# rolety.net
KiCad netlist of a schematic drawn in EAGLE
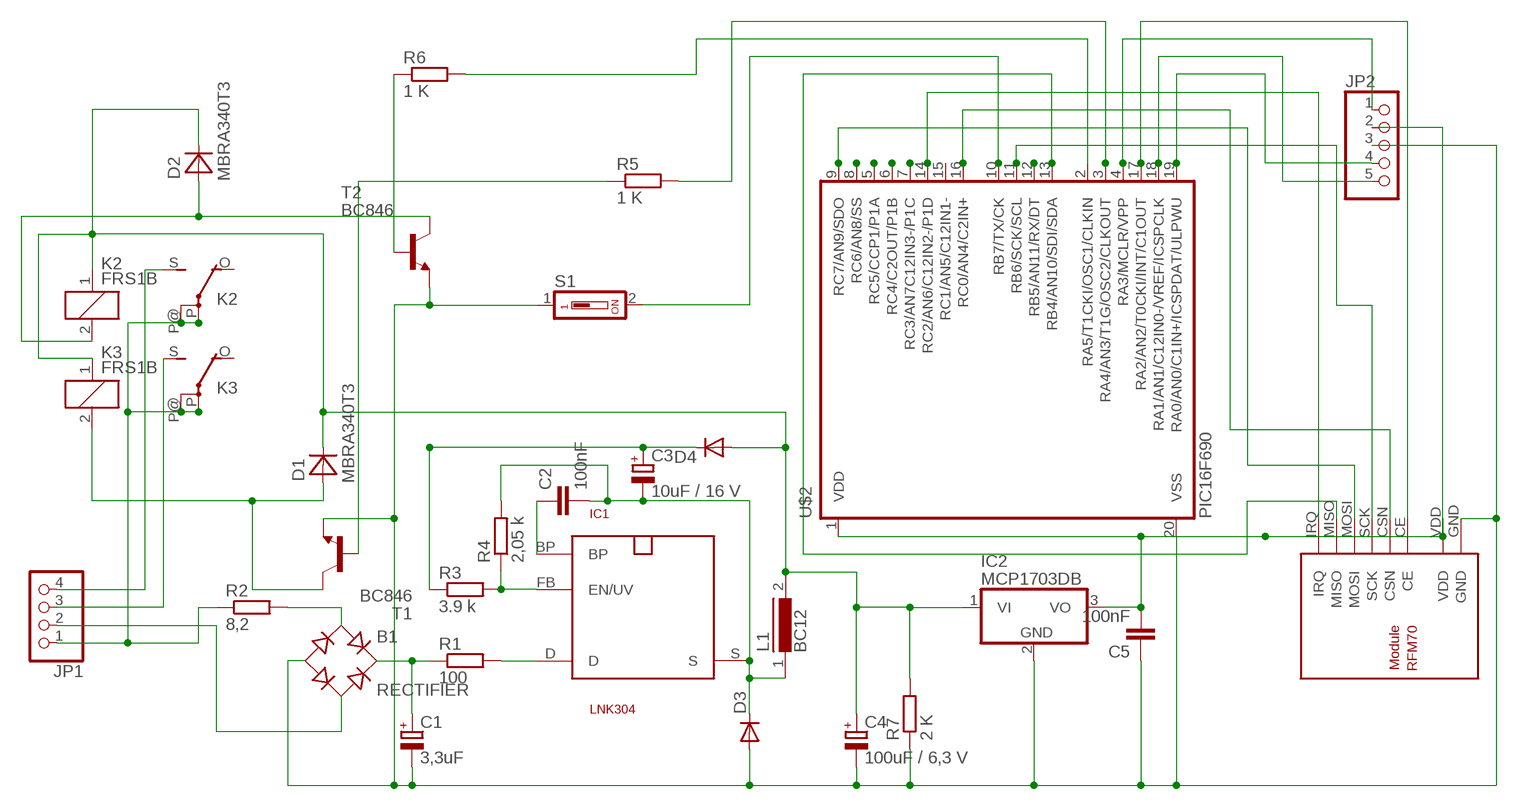
[diagram p0: schematic, sheet 1]

(export (version "E")
  (design (tool "Eeschema 10.0.6"))
  (components
    (comp (ref "B1")
      (value "RECTIFIER")
      (footprint "eagle-import:TO-269AA")
      (libsource (lib "eagle-import") (part "RECTIFIER-S40"))
    )
    (comp (ref "C1")
      (value "3,3uF")
      (footprint "eagle-import:E5-13")
      (libsource (lib "eagle-import") (part "CPOL-EUE5-13"))
    )
    (comp (ref "C2")
      (value "100nF")
      (footprint "eagle-import:C2012")
      (libsource (lib "eagle-import") (part "C-EUC2012"))
    )
    (comp (ref "C3")
      (value "10uF / 16 V")
      (footprint "eagle-import:E2,5-5")
      (libsource (lib "eagle-import") (part "CPOL-EUE2.5-5"))
    )
    (comp (ref "C4")
      (value "100uF / 6,3 V")
      (footprint "eagle-import:E2,5-5")
      (libsource (lib "eagle-import") (part "CPOL-EUE2.5-5"))
    )
    (comp (ref "C5")
      (value "100nF")
      (footprint "eagle-import:C2012")
      (libsource (lib "eagle-import") (part "C-EUC2012"))
    )
    (comp (ref "D1")
      (value "MBRA340T3")
      (footprint "eagle-import:SMA")
      (libsource (lib "eagle-import") (part "MBRA340T3"))
    )
    (comp (ref "D2")
      (value "MBRA340T3")
      (footprint "eagle-import:SMA")
      (libsource (lib "eagle-import") (part "MBRA340T3"))
    )
    (comp (ref "D3")
      (value "DIODE-DO214AA")
      (footprint "eagle-import:DO214AA")
      (libsource (lib "eagle-import") (part "DIODE-DO214AA"))
    )
    (comp (ref "D4")
      (value "DIODE-DO214AA")
      (footprint "eagle-import:DO214AA")
      (libsource (lib "eagle-import") (part "DIODE-DO214AA"))
    )
    (comp (ref "IC1")
      (value "LNK304")
      (footprint "eagle-import:SO-8C")
      (libsource (lib "eagle-import") (part "SO-8C"))
    )
    (comp (ref "IC2")
      (value "MCP1703DB")
      (footprint "eagle-import:SOT223")
      (libsource (lib "eagle-import") (part "MCP1703DB"))
    )
    (comp (ref "JP1")
      (value "PINHD-1X4")
      (footprint "eagle-import:1X04")
      (libsource (lib "eagle-import") (part "PINHD-1X4"))
    )
    (comp (ref "JP2")
      (value "PINHD-1X5")
      (footprint "eagle-import:1X05")
      (libsource (lib "eagle-import") (part "PINHD-1X5"))
    )
    (comp (ref "K2")
      (value "FRS1B")
      (footprint "eagle-import:FRS1B")
      (libsource (lib "eagle-import") (part "FRS1B"))
    )
    (comp (ref "K3")
      (value "FRS1B")
      (footprint "eagle-import:FRS1B")
      (libsource (lib "eagle-import") (part "FRS1B"))
    )
    (comp (ref "L1")
      (value "BC12")
      (footprint "eagle-import:BC12")
      (libsource (lib "eagle-import") (part "BC12"))
    )
    (comp (ref "R1")
      (value "100")
      (footprint "eagle-import:R2512W")
      (libsource (lib "eagle-import") (part "R-EU_R2512W"))
    )
    (comp (ref "R2")
      (value "8,2")
      (footprint "eagle-import:R2512W")
      (libsource (lib "eagle-import") (part "R-EU_R2512W"))
    )
    (comp (ref "R3")
      (value "3.9 k")
      (footprint "eagle-import:M2012")
      (libsource (lib "eagle-import") (part "R-EU_M2012"))
    )
    (comp (ref "R4")
      (value "2,05 k")
      (footprint "eagle-import:M2012")
      (libsource (lib "eagle-import") (part "R-EU_M2012"))
    )
    (comp (ref "R5")
      (value "1 K")
      (footprint "eagle-import:M2012")
      (libsource (lib "eagle-import") (part "R-EU_M2012"))
    )
    (comp (ref "R6")
      (value "1 K")
      (footprint "eagle-import:M2012")
      (libsource (lib "eagle-import") (part "R-EU_M2012"))
    )
    (comp (ref "R7")
      (value "2 K")
      (footprint "eagle-import:M2012")
      (libsource (lib "eagle-import") (part "R-EU_M2012"))
    )
    (comp (ref "S1")
      (value "SD4-01")
      (footprint "eagle-import:SD4-01")
      (libsource (lib "eagle-import") (part "SD4-01"))
    )
    (comp (ref "T1")
      (value "BC846")
      (footprint "eagle-import:SOT23")
      (libsource (lib "eagle-import") (part "BC846"))
    )
    (comp (ref "T2")
      (value "BC846")
      (footprint "eagle-import:SOT23")
      (libsource (lib "eagle-import") (part "BC846"))
    )
    (comp (ref "U$1")
      (value "RFM70")
      (footprint "eagle-import:RFM70")
      (libsource (lib "eagle-import") (part "RFM70"))
    )
    (comp (ref "U$2")
      (value "PIC16F690")
      (footprint "eagle-import:SSOP20")
      (libsource (lib "eagle-import") (part "PIC16F690"))
    )
  )
  (nets
    (net (code "1") (name "Net-(B1-Pad+)") (class "Default")
      (node (ref "B1") (pin "+") (pinfunction "+_+") (pintype "passive"))
      (node (ref "C1") (pin "+") (pinfunction "+_+") (pintype "passive"))
      (node (ref "R1") (pin "1") (pinfunction "1_1") (pintype "passive"))
    )
    (net (code "2") (name "Net-(B1-PadAC1)") (class "Default")
      (node (ref "B1") (pin "AC1") (pinfunction "AC1_AC1") (pintype "passive"))
      (node (ref "R2") (pin "2") (pinfunction "2_2") (pintype "passive"))
    )
    (net (code "3") (name "Net-(B1-PadAC2)") (class "Default")
      (node (ref "B1") (pin "AC2") (pinfunction "AC2_AC2") (pintype "passive"))
      (node (ref "JP1") (pin "2") (pinfunction "2_2") (pintype "passive"))
    )
    (net (code "4") (name "Net-(C2-Pad1)") (class "Default")
      (node (ref "C2") (pin "1") (pinfunction "1_1") (pintype "passive"))
      (node (ref "IC1") (pin "BP") (pinfunction "BP_BP") (pintype "passive"))
    )
    (net (code "5") (name "Net-(C2-Pad2)") (class "Default")
      (node (ref "C2") (pin "2") (pinfunction "2_2") (pintype "passive"))
      (node (ref "C3") (pin "-") (pinfunction "-_-") (pintype "passive"))
      (node (ref "D3") (pin "C") (pinfunction "C_C") (pintype "passive"))
      (node (ref "IC1") (pin "S") (pinfunction "S_S") (pintype "power_in"))
      (node (ref "L1") (pin "1") (pinfunction "1_1") (pintype "passive"))
      (node (ref "R4") (pin "2") (pinfunction "2_2") (pintype "passive"))
    )
    (net (code "6") (name "Net-(C3-Pad+)") (class "Default")
      (node (ref "C3") (pin "+") (pinfunction "+_+") (pintype "passive"))
      (node (ref "D4") (pin "C") (pinfunction "C_C") (pintype "passive"))
      (node (ref "R3") (pin "1") (pinfunction "1_1") (pintype "passive"))
    )
    (net (code "7") (name "Net-(IC1-EN{slash}UV)") (class "Default")
      (node (ref "IC1") (pin "FB") (pinfunction "EN/UV_FB") (pintype "input"))
      (node (ref "R3") (pin "2") (pinfunction "2_2") (pintype "passive"))
      (node (ref "R4") (pin "1") (pinfunction "1_1") (pintype "passive"))
    )
    (net (code "8") (name "Net-(IC1-PadD)") (class "Default")
      (node (ref "IC1") (pin "D") (pinfunction "D_D") (pintype "open_collector"))
      (node (ref "R1") (pin "2") (pinfunction "2_2") (pintype "passive"))
    )
    (net (code "9") (name "Net-(IC2-GND)") (class "Default")
      (node (ref "B1") (pin "-") (pinfunction "-_-") (pintype "passive"))
      (node (ref "C1") (pin "-") (pinfunction "-_-") (pintype "passive"))
      (node (ref "C4") (pin "-") (pinfunction "-_-") (pintype "passive"))
      (node (ref "C5") (pin "1") (pinfunction "1_1") (pintype "passive"))
      (node (ref "D3") (pin "A") (pinfunction "A_A") (pintype "passive"))
      (node (ref "IC2") (pin "2") (pinfunction "GND_2") (pintype "passive"))
      (node (ref "JP2") (pin "3") (pinfunction "3_3") (pintype "passive"))
      (node (ref "R7") (pin "1") (pinfunction "1_1") (pintype "passive"))
      (node (ref "S1") (pin "1") (pinfunction "1_1") (pintype "passive"))
      (node (ref "T1") (pin "2") (pinfunction "E_2") (pintype "passive"))
      (node (ref "T2") (pin "2") (pinfunction "E_2") (pintype "passive"))
      (node (ref "U$1") (pin "GND") (pinfunction "GND_GND") (pintype "power_in"))
      (node (ref "U$2") (pin "20") (pinfunction "VSS_20") (pintype "power_in"))
    )
    (net (code "10") (name "Net-(IC2-VI)") (class "Default")
      (node (ref "C4") (pin "+") (pinfunction "+_+") (pintype "passive"))
      (node (ref "D1") (pin "C") (pinfunction "C_C") (pintype "passive"))
      (node (ref "D2") (pin "C") (pinfunction "C_C") (pintype "passive"))
      (node (ref "D4") (pin "A") (pinfunction "A_A") (pintype "passive"))
      (node (ref "IC2") (pin "1") (pinfunction "VI_1") (pintype "input"))
      (node (ref "K2") (pin "1") (pinfunction "1_1") (pintype "passive"))
      (node (ref "K3") (pin "1") (pinfunction "1_1") (pintype "passive"))
      (node (ref "L1") (pin "2") (pinfunction "2_2") (pintype "passive"))
      (node (ref "R7") (pin "2") (pinfunction "2_2") (pintype "passive"))
    )
    (net (code "11") (name "Net-(IC2-VO)") (class "Default")
      (node (ref "C5") (pin "2") (pinfunction "2_2") (pintype "passive"))
      (node (ref "IC2") (pin "3") (pinfunction "VO_3") (pintype "passive"))
      (node (ref "JP2") (pin "2") (pinfunction "2_2") (pintype "passive"))
      (node (ref "U$1") (pin "VDD") (pinfunction "VDD_VDD") (pintype "power_in"))
      (node (ref "U$2") (pin "1") (pinfunction "VDD_1") (pintype "power_in"))
    )
    (net (code "12") (name "Net-(JP1-Pad1)") (class "Default")
      (node (ref "JP1") (pin "1") (pinfunction "1_1") (pintype "passive"))
      (node (ref "K2") (pin "P") (pinfunction "P_P") (pintype "passive"))
      (node (ref "K2") (pin "P@") (pinfunction "P_P@") (pintype "passive"))
      (node (ref "K3") (pin "P") (pinfunction "P_P") (pintype "passive"))
      (node (ref "K3") (pin "P@") (pinfunction "P_P@") (pintype "passive"))
      (node (ref "R2") (pin "1") (pinfunction "1_1") (pintype "passive"))
    )
    (net (code "13") (name "Net-(JP1-Pad3)") (class "Default")
      (node (ref "JP1") (pin "3") (pinfunction "3_3") (pintype "passive"))
      (node (ref "K3") (pin "S") (pinfunction "S_S") (pintype "passive"))
    )
    (net (code "14") (name "Net-(JP1-Pad4)") (class "Default")
      (node (ref "JP1") (pin "4") (pinfunction "4_4") (pintype "passive"))
      (node (ref "K2") (pin "S") (pinfunction "S_S") (pintype "passive"))
    )
    (net (code "15") (name "Net-(T1-B)") (class "Default")
      (node (ref "R5") (pin "1") (pinfunction "1_1") (pintype "passive"))
      (node (ref "T1") (pin "1") (pinfunction "B_1") (pintype "passive"))
    )
    (net (code "16") (name "Net-(T1-C)") (class "Default")
      (node (ref "D1") (pin "A") (pinfunction "A_A") (pintype "passive"))
      (node (ref "K3") (pin "2") (pinfunction "2_2") (pintype "passive"))
      (node (ref "T1") (pin "3") (pinfunction "C_3") (pintype "passive"))
    )
    (net (code "17") (name "Net-(T2-B)") (class "Default")
      (node (ref "R6") (pin "1") (pinfunction "1_1") (pintype "passive"))
      (node (ref "T2") (pin "1") (pinfunction "B_1") (pintype "passive"))
    )
    (net (code "18") (name "Net-(T2-C)") (class "Default")
      (node (ref "D2") (pin "A") (pinfunction "A_A") (pintype "passive"))
      (node (ref "K2") (pin "2") (pinfunction "2_2") (pintype "passive"))
      (node (ref "T2") (pin "3") (pinfunction "C_3") (pintype "passive"))
    )
    (net (code "19") (name "Net-(U$2-RA0{slash}AN0{slash}C1IN+{slash}ICSPDAT{slash}ULPWU)") (class "Default")
      (node (ref "JP2") (pin "4") (pinfunction "4_4") (pintype "passive"))
      (node (ref "U$2") (pin "19") (pinfunction "RA0/AN0/C1IN+/ICSPDAT/ULPWU_19") (pintype "bidirectional"))
    )
    (net (code "20") (name "Net-(U$2-RA1{slash}AN1{slash}C12IN0-{slash}VREF{slash}ICSPCLK)") (class "Default")
      (node (ref "JP2") (pin "5") (pinfunction "5_5") (pintype "passive"))
      (node (ref "U$2") (pin "18") (pinfunction "RA1/AN1/C12IN0-/VREF/ICSPCLK_18") (pintype "bidirectional"))
    )
    (net (code "21") (name "Net-(U$2-RA2{slash}AN2{slash}T0CKI{slash}INT{slash}C1OUT)") (class "Default")
      (node (ref "U$1") (pin "CE") (pinfunction "CE_CE") (pintype "bidirectional"))
      (node (ref "U$2") (pin "17") (pinfunction "RA2/AN2/T0CKI/INT/C1OUT_17") (pintype "bidirectional"))
    )
    (net (code "22") (name "Net-(U$2-RA3{slash}MCLR{slash}VPP)") (class "Default")
      (node (ref "JP2") (pin "1") (pinfunction "1_1") (pintype "passive"))
      (node (ref "U$2") (pin "4") (pinfunction "RA3/MCLR/VPP_4") (pintype "bidirectional"))
    )
    (net (code "23") (name "Net-(U$2-RA4{slash}AN3{slash}T1G{slash}OSC2{slash}CLKOUT)") (class "Default")
      (node (ref "R5") (pin "2") (pinfunction "2_2") (pintype "passive"))
      (node (ref "U$2") (pin "3") (pinfunction "RA4/AN3/T1G/OSC2/CLKOUT_3") (pintype "bidirectional"))
    )
    (net (code "24") (name "Net-(U$2-RA5{slash}T1CKI{slash}OSC1{slash}CLKIN)") (class "Default")
      (node (ref "R6") (pin "2") (pinfunction "2_2") (pintype "passive"))
      (node (ref "U$2") (pin "2") (pinfunction "RA5/T1CKI/OSC1/CLKIN_2") (pintype "bidirectional"))
    )
    (net (code "25") (name "Net-(U$2-RB4{slash}AN10{slash}SDI{slash}SDA)") (class "Default")
      (node (ref "U$1") (pin "MISO") (pinfunction "MISO_MISO") (pintype "bidirectional"))
      (node (ref "U$2") (pin "13") (pinfunction "RB4/AN10/SDI/SDA_13") (pintype "bidirectional"))
    )
    (net (code "26") (name "Net-(U$2-RB6{slash}SCK{slash}SCL)") (class "Default")
      (node (ref "U$1") (pin "SCK") (pinfunction "SCK_SCK") (pintype "bidirectional"))
      (node (ref "U$2") (pin "11") (pinfunction "RB6/SCK/SCL_11") (pintype "bidirectional"))
    )
    (net (code "27") (name "Net-(U$2-RB7{slash}TX{slash}CK)") (class "Default")
      (node (ref "S1") (pin "2") (pinfunction "2_2") (pintype "passive"))
      (node (ref "U$2") (pin "10") (pinfunction "RB7/TX/CK_10") (pintype "bidirectional"))
    )
    (net (code "28") (name "Net-(U$2-RC0{slash}AN4{slash}C2IN+)") (class "Default")
      (node (ref "U$1") (pin "CSN") (pinfunction "CSN_CSN") (pintype "bidirectional"))
      (node (ref "U$2") (pin "16") (pinfunction "RC0/AN4/C2IN+_16") (pintype "bidirectional"))
    )
    (net (code "29") (name "Net-(U$2-RC2{slash}AN6{slash}C12IN2-{slash}P1D)") (class "Default")
      (node (ref "U$1") (pin "IRQ") (pinfunction "IRQ_IRQ") (pintype "bidirectional"))
      (node (ref "U$2") (pin "14") (pinfunction "RC2/AN6/C12IN2-/P1D_14") (pintype "bidirectional"))
    )
    (net (code "30") (name "Net-(U$2-RC7{slash}AN9{slash}SDO)") (class "Default")
      (node (ref "U$1") (pin "MOSI") (pinfunction "MOSI_MOSI") (pintype "bidirectional"))
      (node (ref "U$2") (pin "9") (pinfunction "RC7/AN9/SDO_9") (pintype "bidirectional"))
    )
    (net (code "31") (name "unconnected-(K2-PadO)") (class "Default")
      (node (ref "K2") (pin "O") (pinfunction "O_O") (pintype "passive"))
    )
    (net (code "32") (name "unconnected-(K3-PadO)") (class "Default")
      (node (ref "K3") (pin "O") (pinfunction "O_O") (pintype "passive"))
    )
    (net (code "33") (name "unconnected-(U$2-RB5{slash}AN11{slash}RX{slash}DT-Pad12)") (class "Default")
      (node (ref "U$2") (pin "12") (pinfunction "RB5/AN11/RX/DT_12") (pintype "bidirectional"))
    )
    (net (code "34") (name "unconnected-(U$2-RC1{slash}AN5{slash}C12IN1--Pad15)") (class "Default")
      (node (ref "U$2") (pin "15") (pinfunction "RC1/AN5/C12IN1-_15") (pintype "bidirectional"))
    )
    (net (code "35") (name "unconnected-(U$2-RC3{slash}AN7C12IN3-{slash}P1C-Pad7)") (class "Default")
      (node (ref "U$2") (pin "7") (pinfunction "RC3/AN7C12IN3-/P1C_7") (pintype "bidirectional"))
    )
    (net (code "36") (name "unconnected-(U$2-RC4{slash}C2OUT{slash}P1B-Pad6)") (class "Default")
      (node (ref "U$2") (pin "6") (pinfunction "RC4/C2OUT/P1B_6") (pintype "bidirectional"))
    )
    (net (code "37") (name "unconnected-(U$2-RC5{slash}CCP1{slash}P1A-Pad5)") (class "Default")
      (node (ref "U$2") (pin "5") (pinfunction "RC5/CCP1/P1A_5") (pintype "bidirectional"))
    )
    (net (code "38") (name "unconnected-(U$2-RC6{slash}AN8{slash}SS-Pad8)") (class "Default")
      (node (ref "U$2") (pin "8") (pinfunction "RC6/AN8/SS_8") (pintype "bidirectional"))
    )
  )
)
